# DriverSchematic.net
KiCad netlist of a schematic drawn in EAGLE
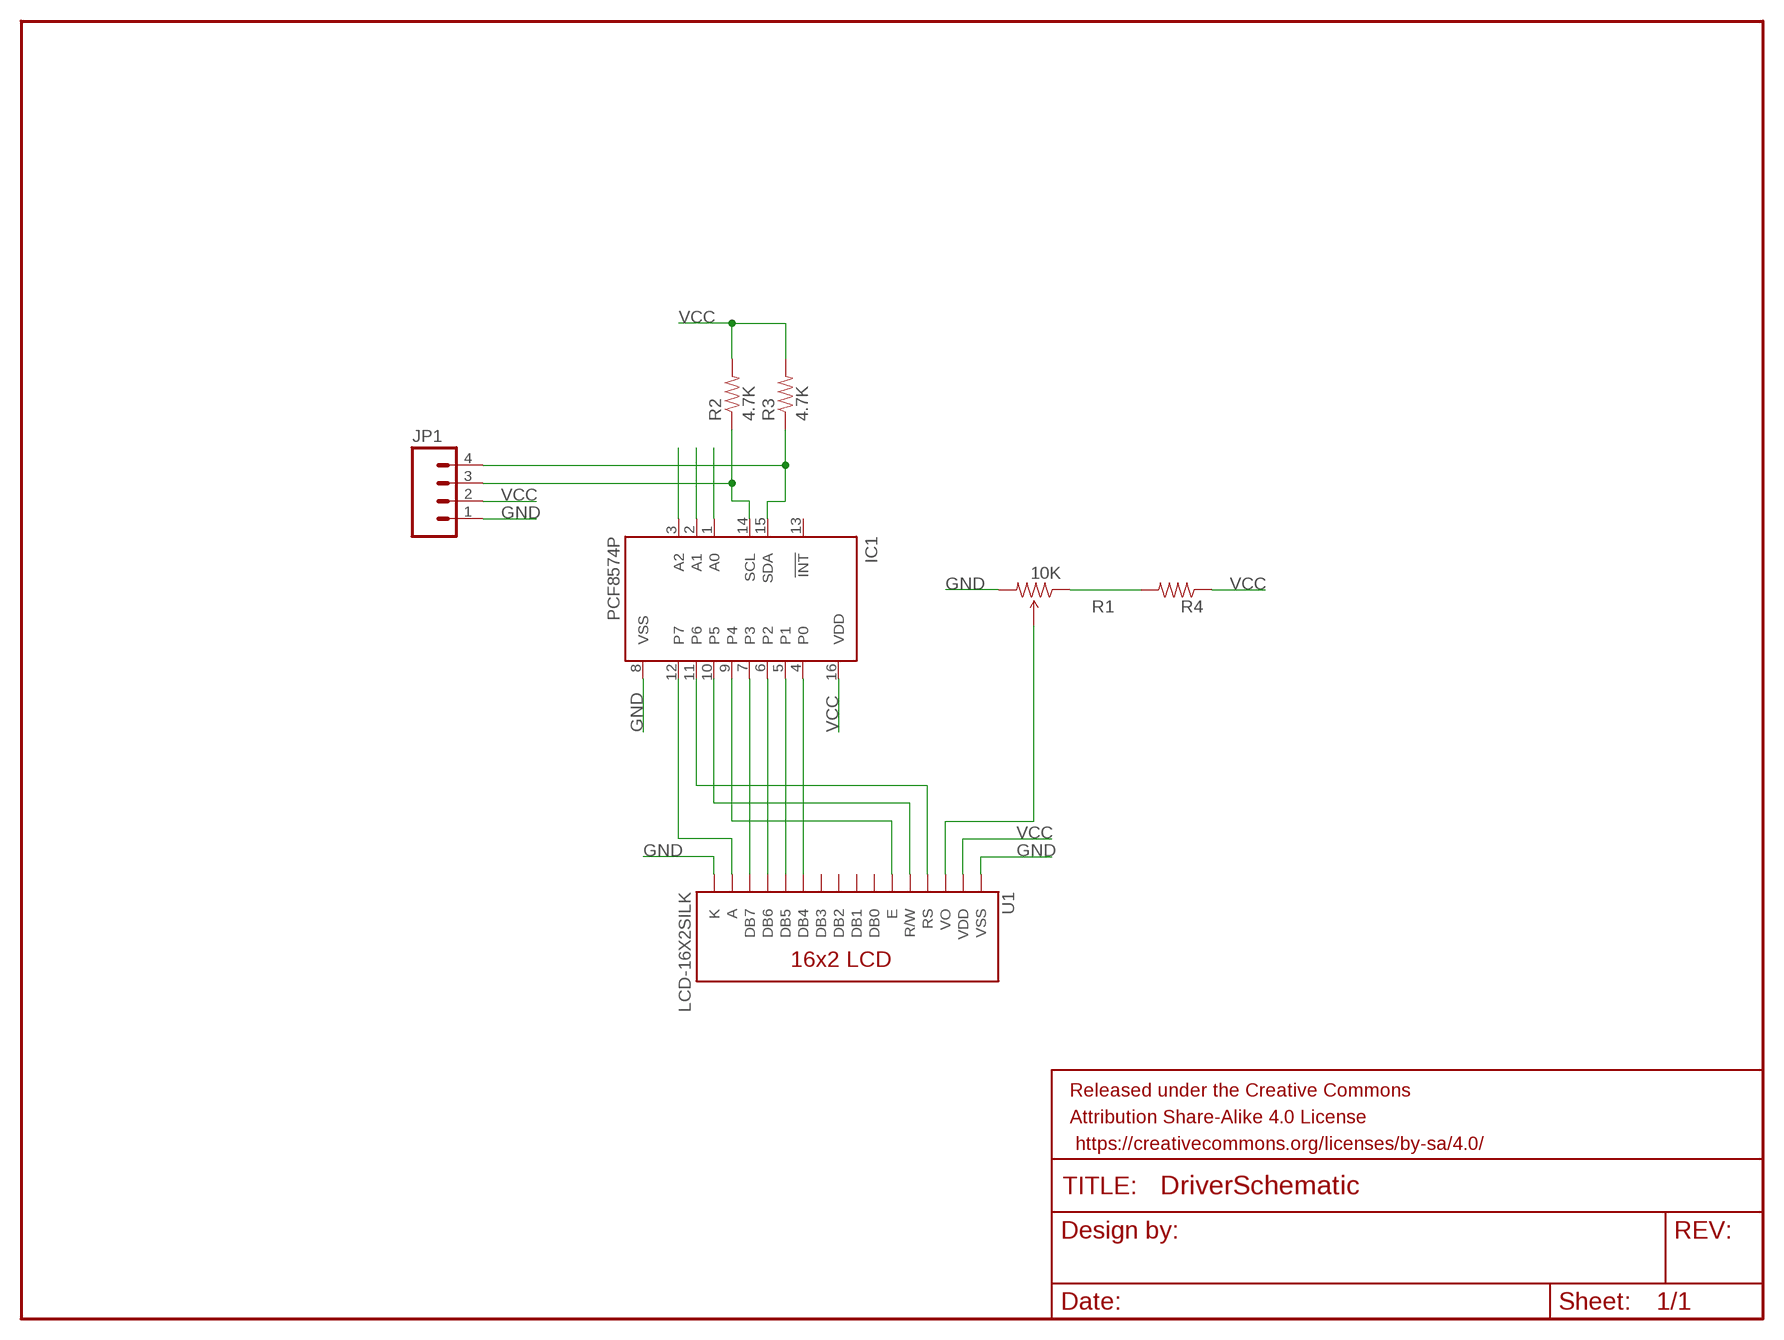
[diagram p0: schematic, sheet 1]

(export (version "E")
  (design (tool "Eeschema 10.0.6"))
  (components
    (comp (ref "FRAME1")
      (value "FRAME-LETTER")
      (footprint "eagle-import:CREATIVE_COMMONS")
      (libsource (lib "eagle-import") (part "FRAME-LETTER"))
    )
    (comp (ref "IC1")
      (value "PCF8574P")
      (footprint "eagle-import:DIL16")
      (fields (field (name "MPN") "PCF8574PN"))
      (libsource (lib "eagle-import") (part "PCF8574P"))
    )
    (comp (ref "JP1")
      (value "M04NO_SILK_ALL_ROUND")
      (footprint "eagle-import:1X04_NO_SILK_ALL_ROUND")
      (libsource (lib "eagle-import") (part "M04NO_SILK_ALL_ROUND"))
    )
    (comp (ref "R1")
      (value "10K")
      (footprint "eagle-import:3386U")
      (libsource (lib "eagle-import") (part "TRIMPOT-PTH-KNOB"))
    )
    (comp (ref "R2")
      (value "4.7K")
      (footprint "eagle-import:1206")
      (libsource (lib "eagle-import") (part "RESISTOR1206"))
    )
    (comp (ref "R3")
      (value "4.7K")
      (footprint "eagle-import:1206")
      (libsource (lib "eagle-import") (part "RESISTOR1206"))
    )
    (comp (ref "R4")
      (value "RESISTOR1206")
      (footprint "eagle-import:1206")
      (libsource (lib "eagle-import") (part "RESISTOR1206"))
    )
    (comp (ref "U1")
      (value "LCD-16X2SILK")
      (footprint "eagle-import:LCD-16X2")
      (libsource (lib "eagle-import") (part "LCD-16X2SILK"))
    )
  )
  (nets
    (net (code "1") (name "/GND") (class "Default")
      (node (ref "IC1") (pin "1") (pinfunction "A0_1") (pintype "input"))
      (node (ref "IC1") (pin "2") (pinfunction "A1_2") (pintype "input"))
      (node (ref "IC1") (pin "3") (pinfunction "A2_3") (pintype "input"))
      (node (ref "IC1") (pin "8") (pinfunction "VSS_8") (pintype "power_in"))
      (node (ref "JP1") (pin "1") (pinfunction "1_1") (pintype "passive"))
      (node (ref "R1") (pin "3") (pinfunction "CW_3") (pintype "passive"))
      (node (ref "U1") (pin "1") (pinfunction "VSS_1") (pintype "power_in"))
      (node (ref "U1") (pin "16") (pinfunction "K_16") (pintype "power_in"))
    )
    (net (code "2") (name "/VCC") (class "Default")
      (node (ref "IC1") (pin "16") (pinfunction "VDD_16") (pintype "power_in"))
      (node (ref "JP1") (pin "2") (pinfunction "2_2") (pintype "passive"))
      (node (ref "R2") (pin "2") (pinfunction "2_2") (pintype "passive"))
      (node (ref "R3") (pin "2") (pinfunction "2_2") (pintype "passive"))
      (node (ref "R4") (pin "1") (pinfunction "1_1") (pintype "passive"))
      (node (ref "U1") (pin "2") (pinfunction "VDD_2") (pintype "power_in"))
    )
    (net (code "3") (name "Net-(IC1-P0)") (class "Default")
      (node (ref "IC1") (pin "4") (pinfunction "P0_4") (pintype "bidirectional"))
      (node (ref "U1") (pin "11") (pinfunction "DB4_11") (pintype "bidirectional"))
    )
    (net (code "4") (name "Net-(IC1-P1)") (class "Default")
      (node (ref "IC1") (pin "5") (pinfunction "P1_5") (pintype "bidirectional"))
      (node (ref "U1") (pin "12") (pinfunction "DB5_12") (pintype "bidirectional"))
    )
    (net (code "5") (name "Net-(IC1-P2)") (class "Default")
      (node (ref "IC1") (pin "6") (pinfunction "P2_6") (pintype "bidirectional"))
      (node (ref "U1") (pin "13") (pinfunction "DB6_13") (pintype "bidirectional"))
    )
    (net (code "6") (name "Net-(IC1-P3)") (class "Default")
      (node (ref "IC1") (pin "7") (pinfunction "P3_7") (pintype "bidirectional"))
      (node (ref "U1") (pin "14") (pinfunction "DB7_14") (pintype "bidirectional"))
    )
    (net (code "7") (name "Net-(IC1-P4)") (class "Default")
      (node (ref "IC1") (pin "9") (pinfunction "P4_9") (pintype "bidirectional"))
      (node (ref "U1") (pin "6") (pinfunction "E_6") (pintype "input"))
    )
    (net (code "8") (name "Net-(IC1-P5)") (class "Default")
      (node (ref "IC1") (pin "10") (pinfunction "P5_10") (pintype "bidirectional"))
      (node (ref "U1") (pin "5") (pinfunction "R/W_5") (pintype "input"))
    )
    (net (code "9") (name "Net-(IC1-P6)") (class "Default")
      (node (ref "IC1") (pin "11") (pinfunction "P6_11") (pintype "bidirectional"))
      (node (ref "U1") (pin "4") (pinfunction "RS_4") (pintype "input"))
    )
    (net (code "10") (name "Net-(IC1-P7)") (class "Default")
      (node (ref "IC1") (pin "12") (pinfunction "P7_12") (pintype "bidirectional"))
      (node (ref "U1") (pin "15") (pinfunction "A_15") (pintype "power_in"))
    )
    (net (code "11") (name "Net-(IC1-SCL)") (class "Default")
      (node (ref "IC1") (pin "14") (pinfunction "SCL_14") (pintype "input"))
      (node (ref "JP1") (pin "3") (pinfunction "3_3") (pintype "passive"))
      (node (ref "R2") (pin "1") (pinfunction "1_1") (pintype "passive"))
    )
    (net (code "12") (name "Net-(IC1-SDA)") (class "Default")
      (node (ref "IC1") (pin "15") (pinfunction "SDA_15") (pintype "bidirectional"))
      (node (ref "JP1") (pin "4") (pinfunction "4_4") (pintype "passive"))
      (node (ref "R3") (pin "1") (pinfunction "1_1") (pintype "passive"))
    )
    (net (code "13") (name "Net-(R1-CCW)") (class "Default")
      (node (ref "R1") (pin "1") (pinfunction "CCW_1") (pintype "passive"))
      (node (ref "R4") (pin "2") (pinfunction "2_2") (pintype "passive"))
    )
    (net (code "14") (name "Net-(R1-WIPER)") (class "Default")
      (node (ref "R1") (pin "2") (pinfunction "WIPER_2") (pintype "passive"))
      (node (ref "U1") (pin "3") (pinfunction "VO_3") (pintype "bidirectional"))
    )
    (net (code "15") (name "unconnected-(IC1-~{INT}-Pad13)") (class "Default")
      (node (ref "IC1") (pin "13") (pinfunction "~{INT}_13") (pintype "output"))
    )
    (net (code "16") (name "unconnected-(U1-DB0-Pad7)") (class "Default")
      (node (ref "U1") (pin "7") (pinfunction "DB0_7") (pintype "bidirectional"))
    )
    (net (code "17") (name "unconnected-(U1-DB1-Pad8)") (class "Default")
      (node (ref "U1") (pin "8") (pinfunction "DB1_8") (pintype "bidirectional"))
    )
    (net (code "18") (name "unconnected-(U1-DB2-Pad9)") (class "Default")
      (node (ref "U1") (pin "9") (pinfunction "DB2_9") (pintype "bidirectional"))
    )
    (net (code "19") (name "unconnected-(U1-DB3-Pad10)") (class "Default")
      (node (ref "U1") (pin "10") (pinfunction "DB3_10") (pintype "bidirectional"))
    )
  )
)
